# OhmCapMeter.net
KiCad netlist of a schematic drawn in Altium Designer
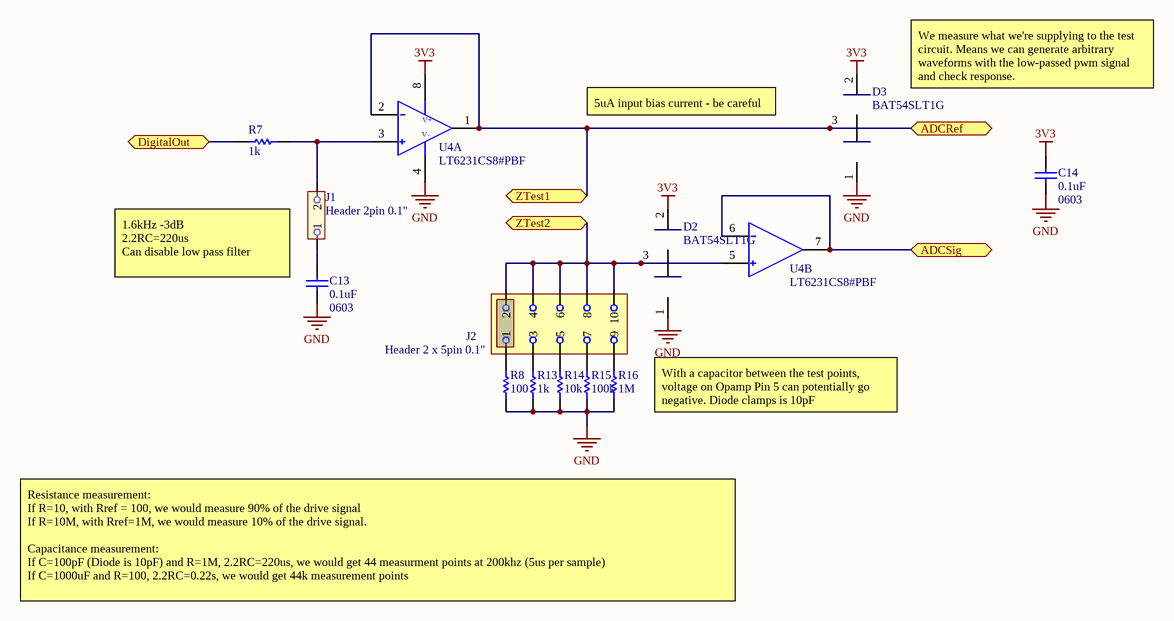
[diagram p0: OhmCapMeter.SchDoc]

(export (version "E")
  (design (tool "Eeschema 10.0.6"))
  (components
    (comp (ref "C13")
      (value "0.1uF")
      (footprint "0603")
      (description "Capacitor, Ceramic, 0603")
      (fields
        (field (name "MANUFACTURER") "Samsung Electro-Mechanics")
        (field (name "MANUFACTURERS PART NUMBER") "CL10A104KA8NNNC")
      )
      (libsource (lib "projectlibrary") (part "Cap0603"))
    )
    (comp (ref "C14")
      (value "0.1uF")
      (footprint "0603")
      (description "Capacitor, Ceramic, 0603")
      (fields
        (field (name "MANUFACTURER") "Samsung Electro-Mechanics")
        (field (name "MANUFACTURERS PART NUMBER") "CL10A104KA8NNNC")
      )
      (libsource (lib "projectlibrary") (part "Cap0603"))
    )
    (comp (ref "D2")
      (value "BAT54SLT1G")
      (footprint "SOT23")
      (fields (field (name "MANUFACTURER") "ON Semiconductor"))
      (libsource (lib "projectlibrary") (part "DiodeClamp"))
    )
    (comp (ref "D3")
      (value "BAT54SLT1G")
      (footprint "SOT23")
      (fields (field (name "MANUFACTURER") "ON Semiconductor"))
      (libsource (lib "projectlibrary") (part "DiodeClamp"))
    )
    (comp (ref "J1")
      (value "Header 2pin 0.1\"")
      (footprint "HDR1X2")
      (description "Header, 0.1\", 2-Pin straight (Any equivalent - may need to be value added)")
      (fields
        (field (name "MANUFACTURER") "Wurth Electronics Inc.")
        (field (name "MANUFACTURERS PART NUMBER") "61300211121")
      )
      (libsource (lib "projectlibrary") (part "Header2"))
    )
    (comp (ref "J2")
      (value "Header 2 x 5pin 0.1\"")
      (footprint "Header2x5")
      (description "Header, 0.1\", 2 row 5 pins")
      (fields
        (field (name "MANUFACTURER") "Wurth Electronics Inc.")
        (field (name "MANUFACTURERS PART NUMBER") "61301021121")
      )
      (libsource (lib "projectlibrary") (part "Header2x5"))
    )
    (comp (ref "R7")
      (value "1k")
      (footprint "0603")
      (description "Resistor")
      (fields
        (field (name "MANUFACTURER") "Yageo")
        (field (name "MANUFACTURERS PART NUMBER") "RC0603FR-071KL")
      )
      (libsource (lib "projectlibrary") (part "Res0603"))
    )
    (comp (ref "R8")
      (value "100")
      (footprint "0603")
      (description "Resistor")
      (fields
        (field (name "MANUFACTURER") "Yageo")
        (field (name "MANUFACTURERS PART NUMBER") "RC0603FR-07100RL")
      )
      (libsource (lib "projectlibrary") (part "Res0603"))
    )
    (comp (ref "R13")
      (value "1k")
      (footprint "0603")
      (description "Resistor")
      (fields
        (field (name "MANUFACTURER") "Yageo")
        (field (name "MANUFACTURERS PART NUMBER") "RC0603FR-071KL")
      )
      (libsource (lib "projectlibrary") (part "Res0603"))
    )
    (comp (ref "R14")
      (value "10k")
      (footprint "0603")
      (description "Resistor")
      (fields
        (field (name "MANUFACTURER") "Yageo")
        (field (name "MANUFACTURERS PART NUMBER") "RC0603FR-0710KL")
      )
      (libsource (lib "projectlibrary") (part "Res0603"))
    )
    (comp (ref "R15")
      (value "100k")
      (footprint "0603")
      (description "Resistor")
      (fields
        (field (name "MANUFACTURER") "Yageo")
        (field (name "MANUFACTURERS PART NUMBER") "AC0603FR-07100KL")
      )
      (libsource (lib "projectlibrary") (part "Res0603"))
    )
    (comp (ref "R16")
      (value "1M")
      (footprint "0603")
      (description "Resistor")
      (fields
        (field (name "MANUFACTURER") "Yageo")
        (field (name "MANUFACTURERS PART NUMBER") "AC0603FR-071ML")
      )
      (libsource (lib "projectlibrary") (part "Res0603"))
    )
    (comp (ref "U4")
      (value "LT6231CS8#PBF")
      (footprint "SO8")
      (description "Dual R-R Opamp Soic 8 70Mhz GBP")
      (fields
        (field (name "MANUFACTURERS PART NUMBER") "LT6231CS8")
        (field (name "MANUFACTURER") "Linear Technology/Analog Devices")
      )
      (libsource (lib "projectlibrary") (part "TSH82IYDT"))
    )
  )
  (nets
    (net (code "1") (name "/ADCRef") (class "Default")
      (node (ref "D3") (pin "3") (pinfunction "3_3") (pintype "passive"))
      (node (ref "U4") (pin "1") (pinfunction "Out_1") (pintype "passive"))
      (node (ref "U4") (pin "2") (pinfunction "IN-_2") (pintype "passive"))
    )
    (net (code "2") (name "/ADCSig") (class "Default")
      (node (ref "U4") (pin "6") (pinfunction "IN-_6") (pintype "passive"))
      (node (ref "U4") (pin "7") (pinfunction "Out_7") (pintype "passive"))
    )
    (net (code "3") (name "/DigitalOut") (class "Default")
      (node (ref "R7") (pin "2") (pinfunction "2_2") (pintype "passive"))
    )
    (net (code "4") (name "/ZTest2") (class "Default")
      (node (ref "D2") (pin "3") (pinfunction "3_3") (pintype "passive"))
      (node (ref "J2") (pin "10") (pinfunction "10_10") (pintype "passive"))
      (node (ref "J2") (pin "2") (pinfunction "2_2") (pintype "passive"))
      (node (ref "J2") (pin "4") (pinfunction "4_4") (pintype "passive"))
      (node (ref "J2") (pin "6") (pinfunction "6_6") (pintype "passive"))
      (node (ref "J2") (pin "8") (pinfunction "8_8") (pintype "passive"))
      (node (ref "U4") (pin "5") (pinfunction "IN+_5") (pintype "passive"))
    )
    (net (code "5") (name "3V3") (class "Default")
      (node (ref "C14") (pin "2") (pinfunction "2_2") (pintype "passive"))
      (node (ref "D2") (pin "2") (pinfunction "2_2") (pintype "passive"))
      (node (ref "D3") (pin "2") (pinfunction "2_2") (pintype "passive"))
      (node (ref "U4") (pin "8") (pinfunction "V+_8") (pintype "power_in"))
    )
    (net (code "6") (name "GND") (class "Default")
      (node (ref "C13") (pin "1") (pinfunction "1_1") (pintype "passive"))
      (node (ref "C14") (pin "1") (pinfunction "1_1") (pintype "passive"))
      (node (ref "D2") (pin "1") (pinfunction "1_1") (pintype "passive"))
      (node (ref "D3") (pin "1") (pinfunction "1_1") (pintype "passive"))
      (node (ref "R13") (pin "1") (pinfunction "1_1") (pintype "passive"))
      (node (ref "R14") (pin "1") (pinfunction "1_1") (pintype "passive"))
      (node (ref "R15") (pin "1") (pinfunction "1_1") (pintype "passive"))
      (node (ref "R16") (pin "1") (pinfunction "1_1") (pintype "passive"))
      (node (ref "R8") (pin "1") (pinfunction "1_1") (pintype "passive"))
      (node (ref "U4") (pin "4") (pinfunction "V-_4") (pintype "power_in"))
    )
    (net (code "7") (name "Net-(C13-Pad2)") (class "Default")
      (node (ref "C13") (pin "2") (pinfunction "2_2") (pintype "passive"))
      (node (ref "J1") (pin "1") (pinfunction "1_1") (pintype "passive"))
    )
    (net (code "8") (name "Net-(J2-Pad1)") (class "Default")
      (node (ref "J2") (pin "1") (pinfunction "1_1") (pintype "passive"))
      (node (ref "R8") (pin "2") (pinfunction "2_2") (pintype "passive"))
    )
    (net (code "9") (name "Net-(J2-Pad3)") (class "Default")
      (node (ref "J2") (pin "3") (pinfunction "3_3") (pintype "passive"))
      (node (ref "R13") (pin "2") (pinfunction "2_2") (pintype "passive"))
    )
    (net (code "10") (name "Net-(J2-Pad5)") (class "Default")
      (node (ref "J2") (pin "5") (pinfunction "5_5") (pintype "passive"))
      (node (ref "R14") (pin "2") (pinfunction "2_2") (pintype "passive"))
    )
    (net (code "11") (name "Net-(J2-Pad7)") (class "Default")
      (node (ref "J2") (pin "7") (pinfunction "7_7") (pintype "passive"))
      (node (ref "R15") (pin "2") (pinfunction "2_2") (pintype "passive"))
    )
    (net (code "12") (name "Net-(J2-Pad9)") (class "Default")
      (node (ref "J2") (pin "9") (pinfunction "9_9") (pintype "passive"))
      (node (ref "R16") (pin "2") (pinfunction "2_2") (pintype "passive"))
    )
    (net (code "13") (name "Net-(U4A-IN+)") (class "Default")
      (node (ref "J1") (pin "2") (pinfunction "2_2") (pintype "passive"))
      (node (ref "R7") (pin "1") (pinfunction "1_1") (pintype "passive"))
      (node (ref "U4") (pin "3") (pinfunction "IN+_3") (pintype "passive"))
    )
  )
)
